# Termoclanok.net
KiCad netlist of a schematic drawn in Altium Designer
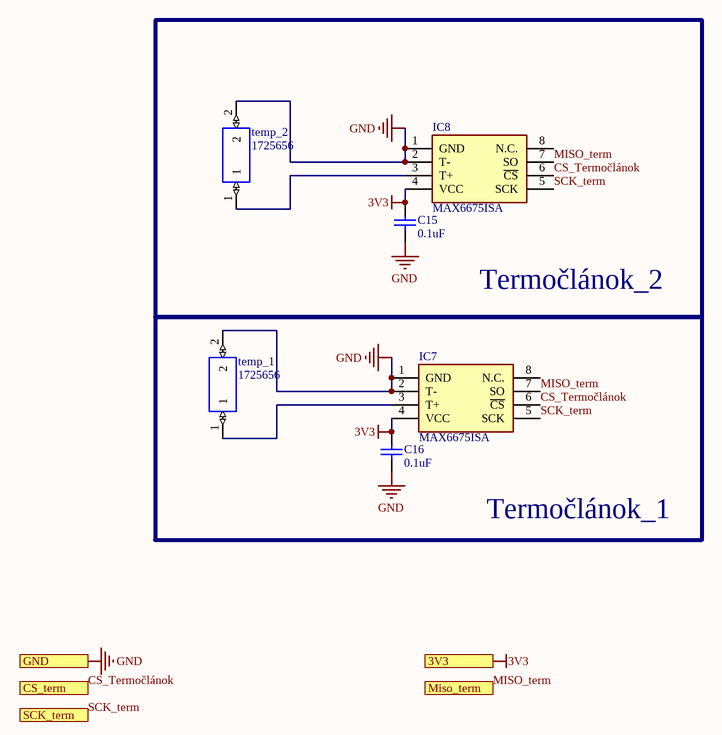
[diagram p0: Termoclanok.SchDoc]

(export (version "E")
  (design (tool "Eeschema 10.0.6"))
  (components
    (comp (ref "C15")
      (value "0.1uF")
      (footprint "1608[0603]")
      (description "Capacitor (Semiconductor SIM Model)")
      (fields (field (name "PUBLISHER") "Altium Limited"))
      (libsource (lib "Miscellaneous Devices") (part "Cap Semi"))
    )
    (comp (ref "C16")
      (value "0.1uF")
      (footprint "1608[0603]")
      (description "Capacitor (Semiconductor SIM Model)")
      (fields (field (name "PUBLISHER") "Altium Limited"))
      (libsource (lib "Miscellaneous Devices") (part "Cap Semi"))
    )
    (comp (ref "IC7")
      (value "MAX6675ISA")
      (footprint "SOIC127P600X175-8N")
      (description "Integrated Circuit")
      (libsource (lib "*") (part "MAX6675ISA"))
    )
    (comp (ref "IC8")
      (value "MAX6675ISA")
      (footprint "SOIC127P600X175-8N")
      (description "Integrated Circuit")
      (libsource (lib "*") (part "MAX6675ISA"))
    )
    (comp (ref "temp_1")
      (value "1725656")
      (footprint "282834-2_1")
      (description "2 way PCB vertical mount terminal,2.54mm 2 way PCB vertical mount terminal,2.54mm")
      (fields (field (name "RS PART NUMBER") "2204260"))
      (libsource (lib "1725656") (part "1725656"))
    )
    (comp (ref "temp_2")
      (value "1725656")
      (footprint "282834-2_1")
      (description "2 way PCB vertical mount terminal,2.54mm 2 way PCB vertical mount terminal,2.54mm")
      (fields (field (name "RS PART NUMBER") "2204260"))
      (libsource (lib "1725656") (part "1725656"))
    )
  )
  (nets
    (net (code "1") (name "/CS_Termočlánok") (class "Default")
      (node (ref "IC7") (pin "6") (pinfunction "~{CS}_6") (pintype "passive"))
      (node (ref "IC8") (pin "6") (pinfunction "~{CS}_6") (pintype "passive"))
    )
    (net (code "2") (name "/MISO_term") (class "Default")
      (node (ref "IC7") (pin "7") (pinfunction "SO_7") (pintype "passive"))
      (node (ref "IC8") (pin "7") (pinfunction "SO_7") (pintype "passive"))
    )
    (net (code "3") (name "/SCK_term") (class "Default")
      (node (ref "IC7") (pin "5") (pinfunction "SCK_5") (pintype "passive"))
      (node (ref "IC8") (pin "5") (pinfunction "SCK_5") (pintype "passive"))
    )
    (net (code "4") (name "3V3") (class "Default")
      (node (ref "C15") (pin "2") (pinfunction "2_2") (pintype "passive"))
      (node (ref "C16") (pin "2") (pinfunction "2_2") (pintype "passive"))
      (node (ref "IC7") (pin "4") (pinfunction "VCC_4") (pintype "passive"))
      (node (ref "IC8") (pin "4") (pinfunction "VCC_4") (pintype "passive"))
    )
    (net (code "5") (name "GND") (class "Default")
      (node (ref "C15") (pin "1") (pinfunction "1_1") (pintype "passive"))
      (node (ref "C16") (pin "1") (pinfunction "1_1") (pintype "passive"))
      (node (ref "IC7") (pin "1") (pinfunction "GND_1") (pintype "passive"))
      (node (ref "IC7") (pin "2") (pinfunction "T-_2") (pintype "passive"))
      (node (ref "IC8") (pin "1") (pinfunction "GND_1") (pintype "passive"))
      (node (ref "IC8") (pin "2") (pinfunction "T-_2") (pintype "passive"))
      (node (ref "temp_1") (pin "2") (pinfunction "2_2") (pintype "bidirectional"))
      (node (ref "temp_2") (pin "2") (pinfunction "2_2") (pintype "bidirectional"))
    )
    (net (code "6") (name "Net-(IC7-T+)") (class "Default")
      (node (ref "IC7") (pin "3") (pinfunction "T+_3") (pintype "passive"))
      (node (ref "temp_1") (pin "1") (pinfunction "1_1") (pintype "bidirectional"))
    )
    (net (code "7") (name "Net-(IC8-T+)") (class "Default")
      (node (ref "IC8") (pin "3") (pinfunction "T+_3") (pintype "passive"))
      (node (ref "temp_2") (pin "1") (pinfunction "1_1") (pintype "bidirectional"))
    )
    (net (code "8") (name "unconnected-(IC7-N.C.-Pad8)") (class "Default")
      (node (ref "IC7") (pin "8") (pinfunction "N.C._8") (pintype "passive"))
    )
    (net (code "9") (name "unconnected-(IC8-N.C.-Pad8)") (class "Default")
      (node (ref "IC8") (pin "8") (pinfunction "N.C._8") (pintype "passive"))
    )
  )
)
